# SCH_Drone_lap_Timer_2024-11-07.net
KiCad netlist of a schematic drawn in EasyEDA
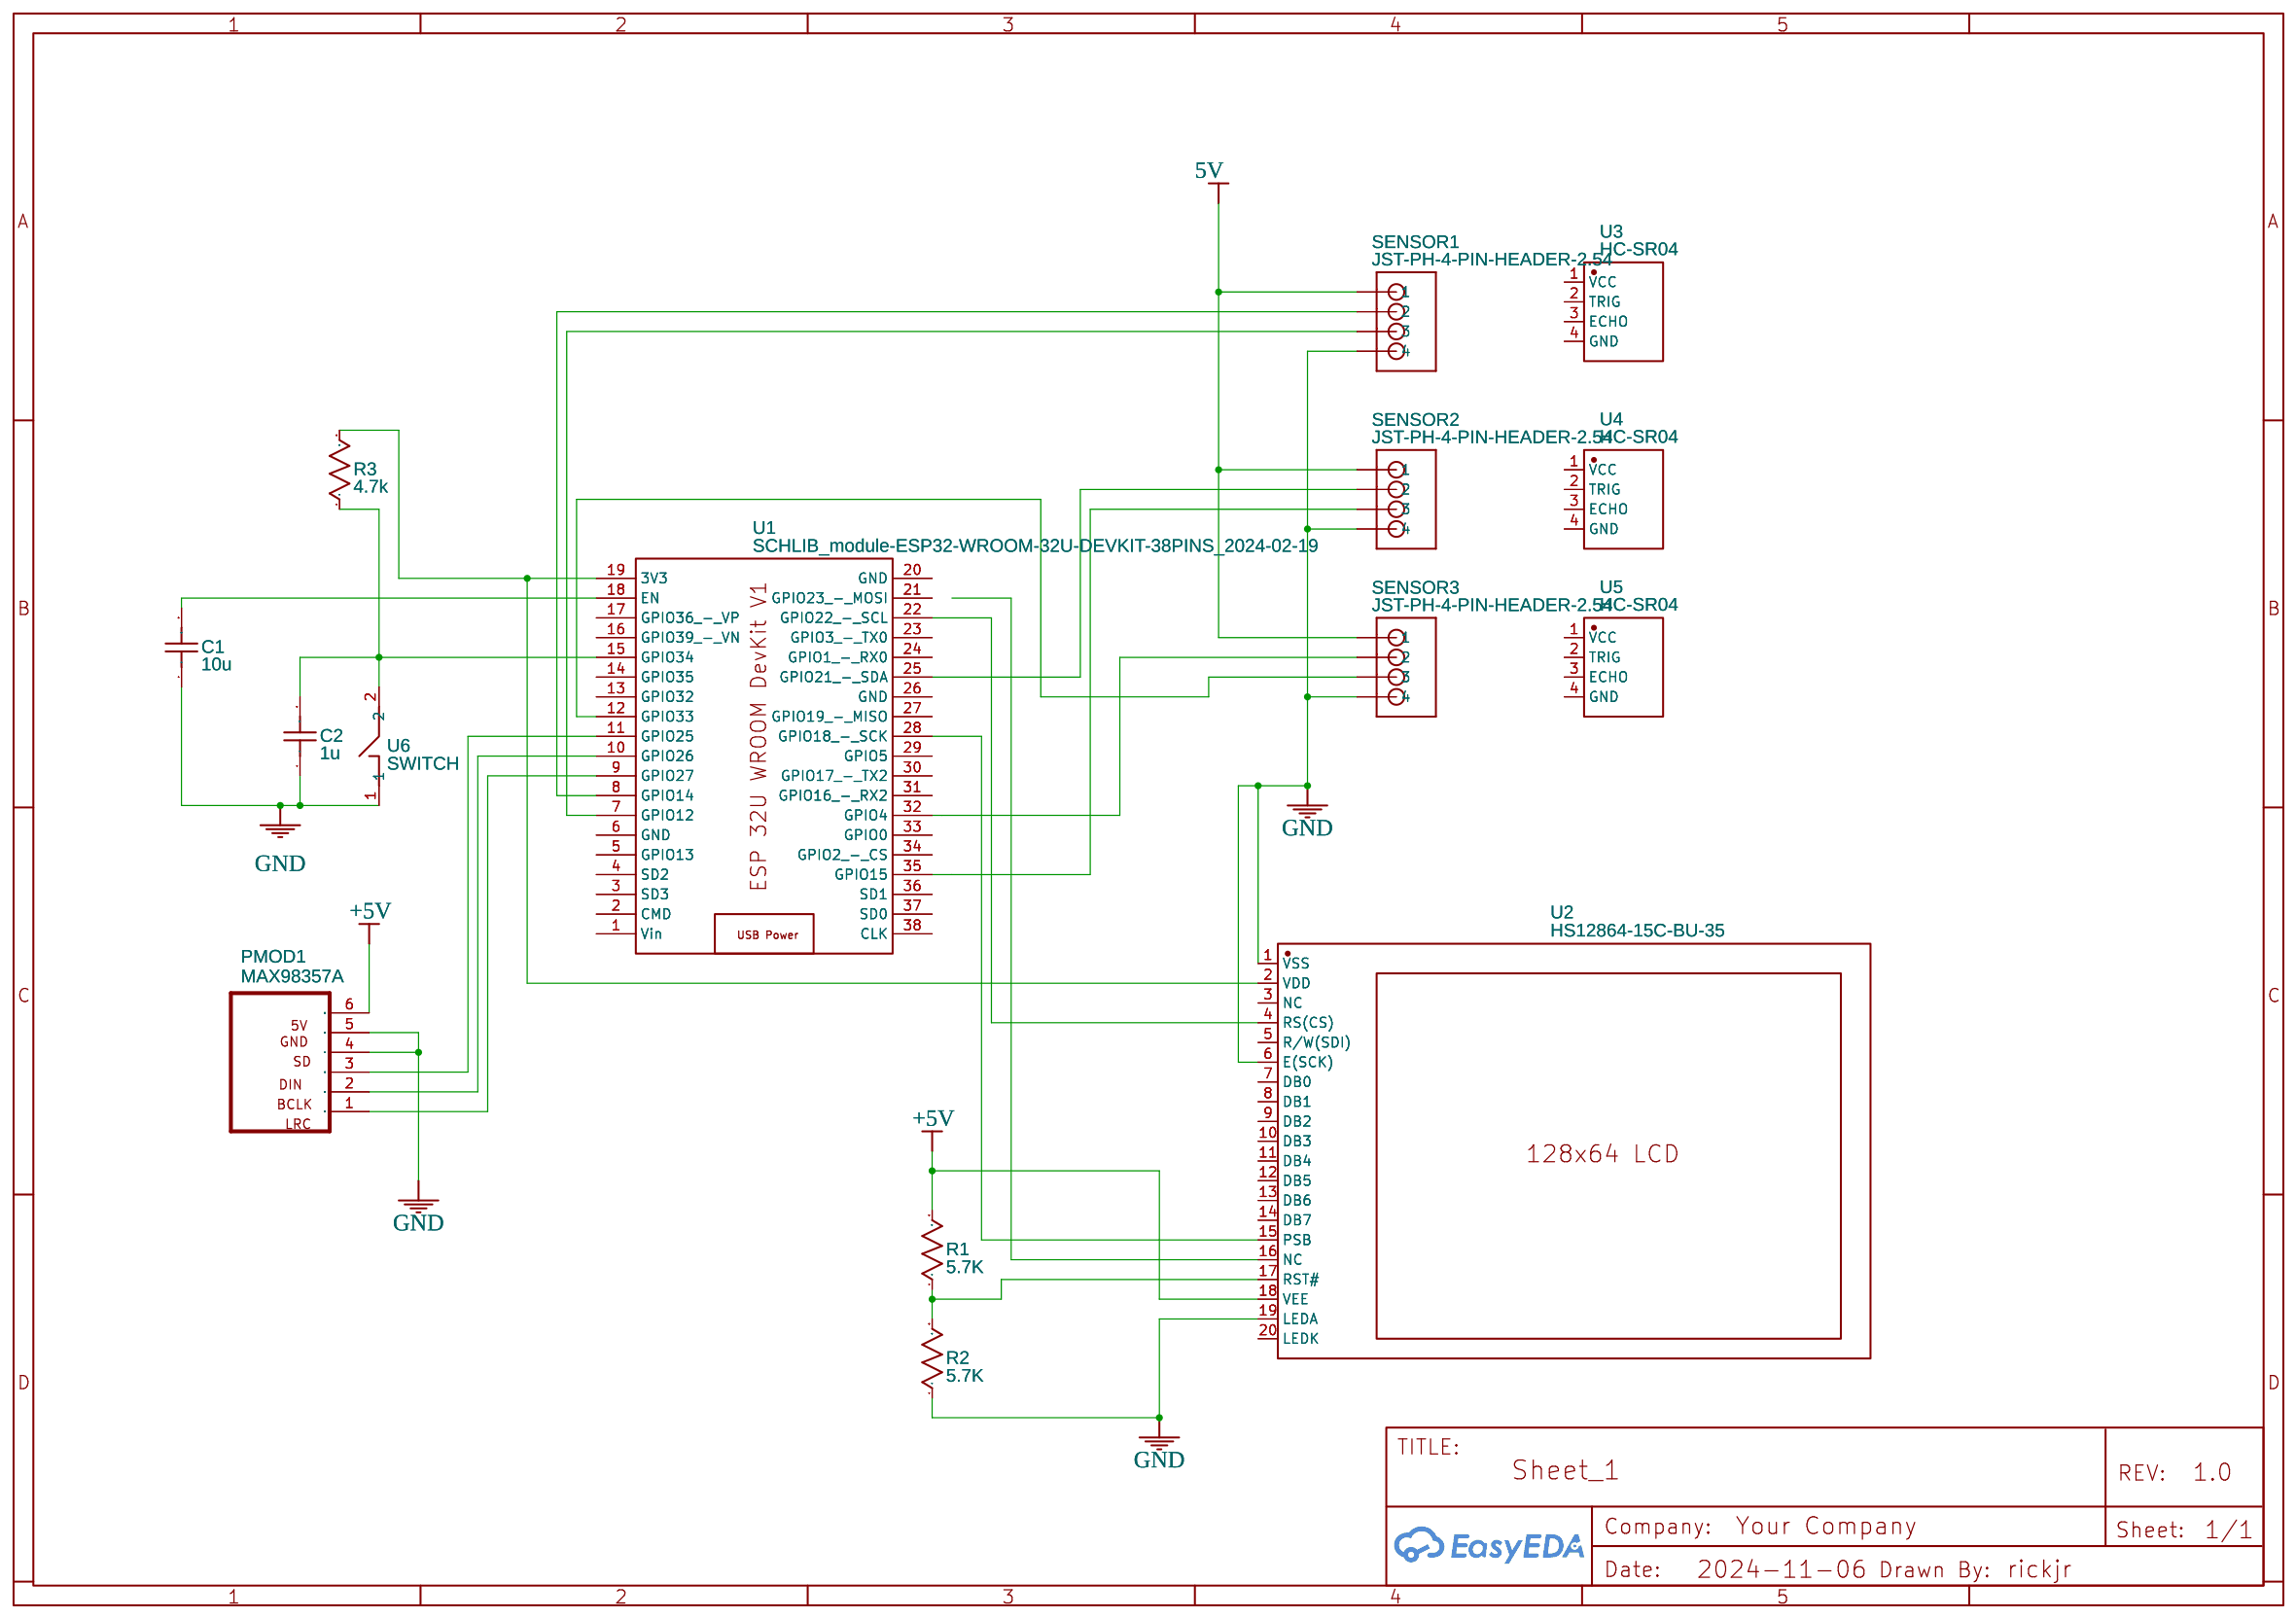
[diagram p0: schematic sheet]

(export (version "E")
  (design (tool "Eeschema 10.0.6"))
  (components
    (comp (ref "C1") (value "10u") (libsource (lib "") (part "C_RAD-0.1_US")))
    (comp (ref "C2") (value "1u") (libsource (lib "") (part "C_RAD-0.1_US")))
    (comp (ref "PMOD1") (value "MAX98357A") (libsource (lib "") (part "PA_PMOD_I2S_SIL_HOST")))
    (comp (ref "R1") (value "5.7K") (libsource (lib "") (part "R_AXIAL-0.5_US")))
    (comp (ref "R2") (value "5.7K") (libsource (lib "") (part "R_AXIAL-0.5_US")))
    (comp (ref "R3") (value "4.7k") (libsource (lib "") (part "R_AXIAL-0.5_US")))
    (comp (ref "SENSOR1")
      (value "JST-PH-4-PIN-HEADER-2.54")
      (libsource (lib "") (part "JST-PH-4-PIN-HEADER-2.54"))
    )
    (comp (ref "SENSOR2")
      (value "JST-PH-4-PIN-HEADER-2.54")
      (libsource (lib "") (part "JST-PH-4-PIN-HEADER-2.54"))
    )
    (comp (ref "SENSOR3")
      (value "JST-PH-4-PIN-HEADER-2.54")
      (libsource (lib "") (part "JST-PH-4-PIN-HEADER-2.54"))
    )
    (comp (ref "U1")
      (value "SCHLIB_module-ESP32-WROOM-32U-DEVKIT-38PINS_2024-02-19")
      (libsource (lib "") (part "SCHLIB_module-ESP32-WROOM-32U-DEVKIT-38PINS_2024-02-19"))
    )
    (comp (ref "U2")
      (value "HS12864-15C-BU-35")
      (fields (field (name "Manufacturer") "HS(汉昇)"))
      (libsource (lib "") (part "HS12864-15C-BU-35"))
    )
    (comp (ref "U3")
      (value "HC-SR04")
      (fields (field (name "Manufacturer") "Universal Microelectronics"))
      (libsource (lib "") (part "HC-SR04"))
    )
    (comp (ref "U4")
      (value "HC-SR04")
      (fields (field (name "Manufacturer") "Universal Microelectronics"))
      (libsource (lib "") (part "HC-SR04"))
    )
    (comp (ref "U5")
      (value "HC-SR04")
      (fields (field (name "Manufacturer") "Universal Microelectronics"))
      (libsource (lib "") (part "HC-SR04"))
    )
    (comp (ref "U6") (value "SWITCH") (libsource (lib "") (part "SWITCH")))
  )
  (nets
    (net (code "1") (name "+5V") (class "Default")
      (node (ref "PMOD1") (pin "6") (pinfunction "6_6") (pintype "unspecified"))
      (node (ref "R1") (pin "2") (pinfunction "2_2") (pintype "unspecified"))
      (node (ref "U2") (pin "18") (pinfunction "VEE_18") (pintype "unspecified"))
    )
    (net (code "2") (name "5V") (class "Default")
      (node (ref "SENSOR1") (pin "1") (pinfunction "1_1") (pintype "unspecified"))
      (node (ref "SENSOR2") (pin "1") (pinfunction "1_1") (pintype "unspecified"))
      (node (ref "SENSOR3") (pin "1") (pinfunction "1_1") (pintype "unspecified"))
    )
    (net (code "3") (name "GND") (class "Default")
      (node (ref "C1") (pin "1") (pinfunction "1_1") (pintype "unspecified"))
      (node (ref "C2") (pin "1") (pinfunction "1_1") (pintype "unspecified"))
      (node (ref "PMOD1") (pin "4") (pinfunction "4_4") (pintype "unspecified"))
      (node (ref "PMOD1") (pin "5") (pinfunction "5_5") (pintype "unspecified"))
      (node (ref "R2") (pin "1") (pinfunction "1_1") (pintype "unspecified"))
      (node (ref "SENSOR1") (pin "4") (pinfunction "4_4") (pintype "unspecified"))
      (node (ref "SENSOR2") (pin "4") (pinfunction "4_4") (pintype "unspecified"))
      (node (ref "SENSOR3") (pin "4") (pinfunction "4_4") (pintype "unspecified"))
      (node (ref "U2") (pin "1") (pinfunction "VSS_1") (pintype "unspecified"))
      (node (ref "U2") (pin "19") (pinfunction "LEDA_19") (pintype "unspecified"))
      (node (ref "U2") (pin "6") (pinfunction "E(SCK)_6") (pintype "unspecified"))
      (node (ref "U6") (pin "1") (pinfunction "1_1") (pintype "unspecified"))
    )
    (net (code "4") (name "Net-(U1-3V3)") (class "Default")
      (node (ref "R3") (pin "2") (pinfunction "2_2") (pintype "unspecified"))
      (node (ref "U1") (pin "19") (pinfunction "3V3_19") (pintype "unspecified"))
      (node (ref "U2") (pin "2") (pinfunction "VDD_2") (pintype "unspecified"))
    )
    (net (code "5") (name "Net-(U1-EN)") (class "Default")
      (node (ref "C1") (pin "2") (pinfunction "2_2") (pintype "unspecified"))
      (node (ref "U1") (pin "18") (pinfunction "EN_18") (pintype "unspecified"))
    )
    (net (code "6") (name "Net-(U1-GPIO4)") (class "Default")
      (node (ref "SENSOR3") (pin "2") (pinfunction "2_2") (pintype "unspecified"))
      (node (ref "U1") (pin "32") (pinfunction "GPIO4_32") (pintype "unspecified"))
    )
    (net (code "7") (name "Net-(U1-GPIO12)") (class "Default")
      (node (ref "SENSOR1") (pin "3") (pinfunction "3_3") (pintype "unspecified"))
      (node (ref "U1") (pin "7") (pinfunction "GPIO12_7") (pintype "unspecified"))
    )
    (net (code "8") (name "Net-(U1-GPIO14)") (class "Default")
      (node (ref "SENSOR1") (pin "2") (pinfunction "2_2") (pintype "unspecified"))
      (node (ref "U1") (pin "8") (pinfunction "GPIO14_8") (pintype "unspecified"))
    )
    (net (code "9") (name "Net-(U1-GPIO15)") (class "Default")
      (node (ref "SENSOR2") (pin "3") (pinfunction "3_3") (pintype "unspecified"))
      (node (ref "U1") (pin "35") (pinfunction "GPIO15_35") (pintype "unspecified"))
    )
    (net (code "10") (name "Net-(U1-GPIO18_-_SCK)") (class "Default")
      (node (ref "U1") (pin "28") (pinfunction "GPIO18_-_SCK_28") (pintype "unspecified"))
      (node (ref "U2") (pin "15") (pinfunction "PSB_15") (pintype "unspecified"))
    )
    (net (code "11") (name "Net-(U1-GPIO21_-_SDA)") (class "Default")
      (node (ref "SENSOR2") (pin "2") (pinfunction "2_2") (pintype "unspecified"))
      (node (ref "U1") (pin "25") (pinfunction "GPIO21_-_SDA_25") (pintype "unspecified"))
    )
    (net (code "12") (name "Net-(U1-GPIO22_-_SCL)") (class "Default")
      (node (ref "U1") (pin "22") (pinfunction "GPIO22_-_SCL_22") (pintype "unspecified"))
      (node (ref "U2") (pin "4") (pinfunction "RS(CS)_4") (pintype "unspecified"))
    )
    (net (code "13") (name "Net-(U1-GPIO25)") (class "Default")
      (node (ref "PMOD1") (pin "3") (pinfunction "3_3") (pintype "unspecified"))
      (node (ref "U1") (pin "11") (pinfunction "GPIO25_11") (pintype "unspecified"))
    )
    (net (code "14") (name "Net-(U1-GPIO26)") (class "Default")
      (node (ref "PMOD1") (pin "2") (pinfunction "2_2") (pintype "unspecified"))
      (node (ref "U1") (pin "10") (pinfunction "GPIO26_10") (pintype "unspecified"))
    )
    (net (code "15") (name "Net-(U1-GPIO27)") (class "Default")
      (node (ref "PMOD1") (pin "1") (pinfunction "1_1") (pintype "unspecified"))
      (node (ref "U1") (pin "9") (pinfunction "GPIO27_9") (pintype "unspecified"))
    )
    (net (code "16") (name "Net-(U1-GPIO33)") (class "Default")
      (node (ref "SENSOR3") (pin "3") (pinfunction "3_3") (pintype "unspecified"))
      (node (ref "U1") (pin "12") (pinfunction "GPIO33_12") (pintype "unspecified"))
    )
    (net (code "17") (name "Net-(U1-GPIO34)") (class "Default")
      (node (ref "C2") (pin "2") (pinfunction "2_2") (pintype "unspecified"))
      (node (ref "R3") (pin "1") (pinfunction "1_1") (pintype "unspecified"))
      (node (ref "U1") (pin "15") (pinfunction "GPIO34_15") (pintype "unspecified"))
      (node (ref "U6") (pin "2") (pinfunction "2_2") (pintype "unspecified"))
    )
    (net (code "18") (name "Net-(U2-RST#)") (class "Default")
      (node (ref "R1") (pin "1") (pinfunction "1_1") (pintype "unspecified"))
      (node (ref "R2") (pin "2") (pinfunction "2_2") (pintype "unspecified"))
      (node (ref "U2") (pin "17") (pinfunction "RST#_17") (pintype "unspecified"))
    )
    (net (code "19") (name "unconnected-(U1-CLK-Pad38)") (class "Default")
      (node (ref "U1") (pin "38") (pinfunction "CLK_38") (pintype "unspecified"))
    )
    (net (code "20") (name "unconnected-(U1-CMD-Pad2)") (class "Default")
      (node (ref "U1") (pin "2") (pinfunction "CMD_2") (pintype "unspecified"))
    )
    (net (code "21") (name "unconnected-(U1-GND-Pad6)") (class "Default")
      (node (ref "U1") (pin "6") (pinfunction "GND_6") (pintype "unspecified"))
    )
    (net (code "22") (name "unconnected-(U1-GND-Pad20)") (class "Default")
      (node (ref "U1") (pin "20") (pinfunction "GND_20") (pintype "unspecified"))
    )
    (net (code "23") (name "unconnected-(U1-GND-Pad26)") (class "Default")
      (node (ref "U1") (pin "26") (pinfunction "GND_26") (pintype "unspecified"))
    )
    (net (code "24") (name "unconnected-(U1-GPIO0-Pad33)") (class "Default")
      (node (ref "U1") (pin "33") (pinfunction "GPIO0_33") (pintype "unspecified"))
    )
    (net (code "25") (name "unconnected-(U1-GPIO1_-_RX0-Pad24)") (class "Default")
      (node (ref "U1") (pin "24") (pinfunction "GPIO1_-_RX0_24") (pintype "unspecified"))
    )
    (net (code "26") (name "unconnected-(U1-GPIO2_-_CS-Pad34)") (class "Default")
      (node (ref "U1") (pin "34") (pinfunction "GPIO2_-_CS_34") (pintype "unspecified"))
    )
    (net (code "27") (name "unconnected-(U1-GPIO3_-_TX0-Pad23)") (class "Default")
      (node (ref "U1") (pin "23") (pinfunction "GPIO3_-_TX0_23") (pintype "unspecified"))
    )
    (net (code "28") (name "unconnected-(U1-GPIO5-Pad29)") (class "Default")
      (node (ref "U1") (pin "29") (pinfunction "GPIO5_29") (pintype "unspecified"))
    )
    (net (code "29") (name "unconnected-(U1-GPIO13-Pad5)") (class "Default")
      (node (ref "U1") (pin "5") (pinfunction "GPIO13_5") (pintype "unspecified"))
    )
    (net (code "30") (name "unconnected-(U1-GPIO16_-_RX2-Pad31)") (class "Default")
      (node (ref "U1") (pin "31") (pinfunction "GPIO16_-_RX2_31") (pintype "unspecified"))
    )
    (net (code "31") (name "unconnected-(U1-GPIO17_-_TX2-Pad30)") (class "Default")
      (node (ref "U1") (pin "30") (pinfunction "GPIO17_-_TX2_30") (pintype "unspecified"))
    )
    (net (code "32") (name "unconnected-(U1-GPIO19_-_MISO-Pad27)") (class "Default")
      (node (ref "U1") (pin "27") (pinfunction "GPIO19_-_MISO_27") (pintype "unspecified"))
    )
    (net (code "33") (name "unconnected-(U1-GPIO23_-_MOSI-Pad21)") (class "Default")
      (node (ref "U1") (pin "21") (pinfunction "GPIO23_-_MOSI_21") (pintype "unspecified"))
    )
    (net (code "34") (name "unconnected-(U1-GPIO32-Pad13)") (class "Default")
      (node (ref "U1") (pin "13") (pinfunction "GPIO32_13") (pintype "unspecified"))
    )
    (net (code "35") (name "unconnected-(U1-GPIO35-Pad14)") (class "Default")
      (node (ref "U1") (pin "14") (pinfunction "GPIO35_14") (pintype "unspecified"))
    )
    (net (code "36") (name "unconnected-(U1-GPIO36_-_VP-Pad17)") (class "Default")
      (node (ref "U1") (pin "17") (pinfunction "GPIO36_-_VP_17") (pintype "unspecified"))
    )
    (net (code "37") (name "unconnected-(U1-GPIO39_-_VN-Pad16)") (class "Default")
      (node (ref "U1") (pin "16") (pinfunction "GPIO39_-_VN_16") (pintype "unspecified"))
    )
    (net (code "38") (name "unconnected-(U1-SD0-Pad37)") (class "Default")
      (node (ref "U1") (pin "37") (pinfunction "SD0_37") (pintype "unspecified"))
    )
    (net (code "39") (name "unconnected-(U1-SD1-Pad36)") (class "Default")
      (node (ref "U1") (pin "36") (pinfunction "SD1_36") (pintype "unspecified"))
    )
    (net (code "40") (name "unconnected-(U1-SD2-Pad4)") (class "Default")
      (node (ref "U1") (pin "4") (pinfunction "SD2_4") (pintype "unspecified"))
    )
    (net (code "41") (name "unconnected-(U1-SD3-Pad3)") (class "Default")
      (node (ref "U1") (pin "3") (pinfunction "SD3_3") (pintype "unspecified"))
    )
    (net (code "42") (name "unconnected-(U1-Vin-Pad1)") (class "Default")
      (node (ref "U1") (pin "1") (pinfunction "Vin_1") (pintype "unspecified"))
    )
    (net (code "43") (name "unconnected-(U2-DB0-Pad7)") (class "Default")
      (node (ref "U2") (pin "7") (pinfunction "DB0_7") (pintype "unspecified"))
    )
    (net (code "44") (name "unconnected-(U2-DB1-Pad8)") (class "Default")
      (node (ref "U2") (pin "8") (pinfunction "DB1_8") (pintype "unspecified"))
    )
    (net (code "45") (name "unconnected-(U2-DB2-Pad9)") (class "Default")
      (node (ref "U2") (pin "9") (pinfunction "DB2_9") (pintype "unspecified"))
    )
    (net (code "46") (name "unconnected-(U2-DB3-Pad10)") (class "Default")
      (node (ref "U2") (pin "10") (pinfunction "DB3_10") (pintype "unspecified"))
    )
    (net (code "47") (name "unconnected-(U2-DB4-Pad11)") (class "Default")
      (node (ref "U2") (pin "11") (pinfunction "DB4_11") (pintype "unspecified"))
    )
    (net (code "48") (name "unconnected-(U2-DB5-Pad12)") (class "Default")
      (node (ref "U2") (pin "12") (pinfunction "DB5_12") (pintype "unspecified"))
    )
    (net (code "49") (name "unconnected-(U2-DB6-Pad13)") (class "Default")
      (node (ref "U2") (pin "13") (pinfunction "DB6_13") (pintype "unspecified"))
    )
    (net (code "50") (name "unconnected-(U2-DB7-Pad14)") (class "Default")
      (node (ref "U2") (pin "14") (pinfunction "DB7_14") (pintype "unspecified"))
    )
    (net (code "51") (name "unconnected-(U2-LEDK-Pad20)") (class "Default")
      (node (ref "U2") (pin "20") (pinfunction "LEDK_20") (pintype "unspecified"))
    )
    (net (code "52") (name "unconnected-(U2-NC-Pad3)") (class "Default")
      (node (ref "U2") (pin "3") (pinfunction "NC_3") (pintype "unspecified"))
    )
    (net (code "53") (name "unconnected-(U2-NC-Pad16)") (class "Default")
      (node (ref "U2") (pin "16") (pinfunction "NC_16") (pintype "unspecified"))
    )
    (net (code "54") (name "unconnected-(U2-R{slash}W(SDI)-Pad5)") (class "Default")
      (node (ref "U2") (pin "5") (pinfunction "R/W(SDI)_5") (pintype "unspecified"))
    )
    (net (code "55") (name "unconnected-(U3-ECHO-Pad3)") (class "Default")
      (node (ref "U3") (pin "3") (pinfunction "ECHO_3") (pintype "unspecified"))
    )
    (net (code "56") (name "unconnected-(U3-GND-Pad4)") (class "Default")
      (node (ref "U3") (pin "4") (pinfunction "GND_4") (pintype "unspecified"))
    )
    (net (code "57") (name "unconnected-(U3-TRIG-Pad2)") (class "Default")
      (node (ref "U3") (pin "2") (pinfunction "TRIG_2") (pintype "unspecified"))
    )
    (net (code "58") (name "unconnected-(U3-VCC-Pad1)") (class "Default")
      (node (ref "U3") (pin "1") (pinfunction "VCC_1") (pintype "unspecified"))
    )
    (net (code "59") (name "unconnected-(U4-ECHO-Pad3)") (class "Default")
      (node (ref "U4") (pin "3") (pinfunction "ECHO_3") (pintype "unspecified"))
    )
    (net (code "60") (name "unconnected-(U4-GND-Pad4)") (class "Default")
      (node (ref "U4") (pin "4") (pinfunction "GND_4") (pintype "unspecified"))
    )
    (net (code "61") (name "unconnected-(U4-TRIG-Pad2)") (class "Default")
      (node (ref "U4") (pin "2") (pinfunction "TRIG_2") (pintype "unspecified"))
    )
    (net (code "62") (name "unconnected-(U4-VCC-Pad1)") (class "Default")
      (node (ref "U4") (pin "1") (pinfunction "VCC_1") (pintype "unspecified"))
    )
    (net (code "63") (name "unconnected-(U5-ECHO-Pad3)") (class "Default")
      (node (ref "U5") (pin "3") (pinfunction "ECHO_3") (pintype "unspecified"))
    )
    (net (code "64") (name "unconnected-(U5-GND-Pad4)") (class "Default")
      (node (ref "U5") (pin "4") (pinfunction "GND_4") (pintype "unspecified"))
    )
    (net (code "65") (name "unconnected-(U5-TRIG-Pad2)") (class "Default")
      (node (ref "U5") (pin "2") (pinfunction "TRIG_2") (pintype "unspecified"))
    )
    (net (code "66") (name "unconnected-(U5-VCC-Pad1)") (class "Default")
      (node (ref "U5") (pin "1") (pinfunction "VCC_1") (pintype "unspecified"))
    )
  )
)
